# Main_MCU_NuM487KM.net
KiCad netlist of a schematic drawn in Altium Designer
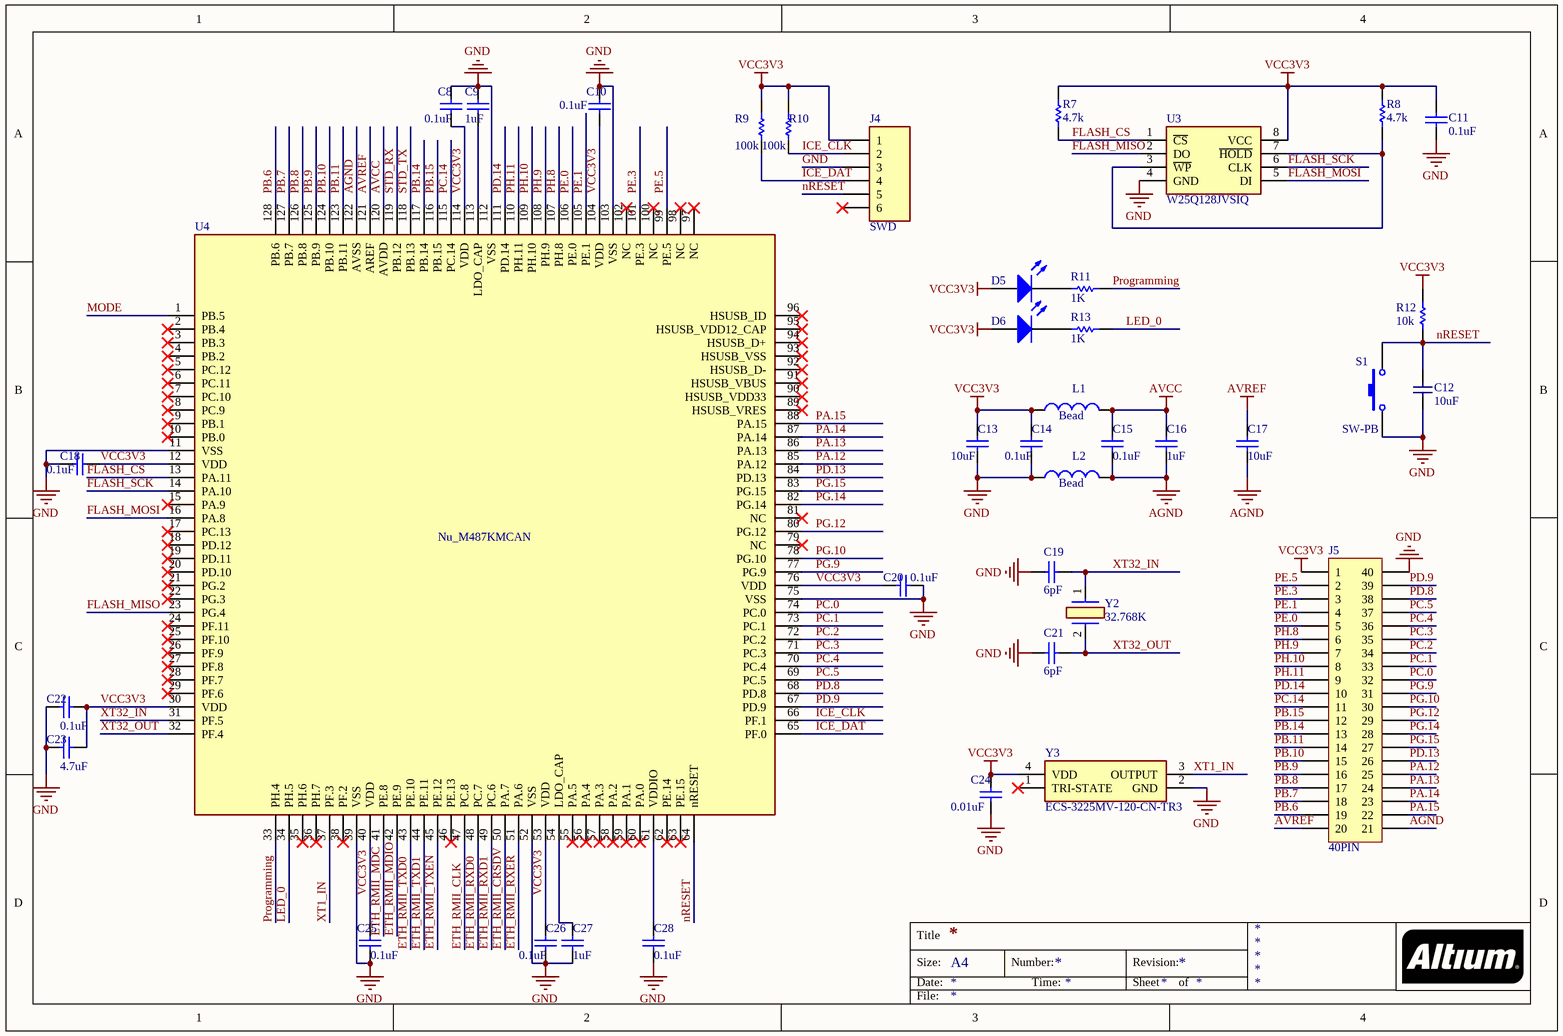
[diagram p0: Main_MCU_NuM487KM.SchDoc]

(export (version "E")
  (design (tool "Eeschema 10.0.6"))
  (components
    (comp (ref "C8")
      (value "0.1uF")
      (footprint "SMD0603")
      (description "Capacitor (Semiconductor SIM Model)")
      (fields (field (name "PUBLISHER") "Altium Limited"))
      (libsource (lib "Miscellaneous Devices") (part "Cap Semi"))
    )
    (comp (ref "C9")
      (value "1uF")
      (footprint "SMD0603")
      (description "Capacitor (Semiconductor SIM Model)")
      (fields (field (name "PUBLISHER") "Altium Limited"))
      (libsource (lib "Miscellaneous Devices") (part "Cap Semi"))
    )
    (comp (ref "C10")
      (value "0.1uF")
      (footprint "SMD0603")
      (description "Capacitor (Semiconductor SIM Model)")
      (fields (field (name "PUBLISHER") "Altium Limited"))
      (libsource (lib "Miscellaneous Devices") (part "Cap Semi"))
    )
    (comp (ref "C11")
      (value "0.1uF")
      (footprint "SMD0603")
      (description "Capacitor (Semiconductor SIM Model)")
      (fields (field (name "PUBLISHER") "Altium Limited"))
      (libsource (lib "Miscellaneous Devices") (part "Cap Semi"))
    )
    (comp (ref "C12")
      (value "10uF")
      (footprint "SMD0603")
      (description "Capacitor (Semiconductor SIM Model)")
      (libsource (lib "SRV8") (part "Cap"))
    )
    (comp (ref "C13")
      (value "10uF")
      (footprint "SMD0603")
      (description "Capacitor (Semiconductor SIM Model)")
      (fields (field (name "PUBLISHER") "Altium Limited"))
      (libsource (lib "Miscellaneous Devices") (part "Cap Semi"))
    )
    (comp (ref "C14")
      (value "0.1uF")
      (footprint "SMD0603")
      (description "Capacitor (Semiconductor SIM Model)")
      (fields (field (name "PUBLISHER") "Altium Limited"))
      (libsource (lib "Miscellaneous Devices") (part "Cap Semi"))
    )
    (comp (ref "C15")
      (value "0.1uF")
      (footprint "SMD0603")
      (description "Capacitor (Semiconductor SIM Model)")
      (fields (field (name "PUBLISHER") "Altium Limited"))
      (libsource (lib "Miscellaneous Devices") (part "Cap Semi"))
    )
    (comp (ref "C16")
      (value "1uF")
      (footprint "SMD0603")
      (description "Capacitor (Semiconductor SIM Model)")
      (fields (field (name "PUBLISHER") "Altium Limited"))
      (libsource (lib "Miscellaneous Devices") (part "Cap Semi"))
    )
    (comp (ref "C17")
      (value "10uF")
      (footprint "SMD0603")
      (description "Capacitor (Semiconductor SIM Model)")
      (fields (field (name "PUBLISHER") "Altium Limited"))
      (libsource (lib "Miscellaneous Devices") (part "Cap Semi"))
    )
    (comp (ref "C18")
      (value "0.1uF")
      (footprint "SMD0603")
      (description "Capacitor (Semiconductor SIM Model)")
      (fields (field (name "PUBLISHER") "Altium Limited"))
      (libsource (lib "Miscellaneous Devices") (part "Cap Semi"))
    )
    (comp (ref "C19")
      (value "6pF")
      (footprint "SMD0603")
      (description "Capacitor (Semiconductor SIM Model)")
      (fields (field (name "PUBLISHER") "Altium Limited"))
      (libsource (lib "Miscellaneous Devices") (part "Cap Semi"))
    )
    (comp (ref "C20")
      (value "0.1uF")
      (footprint "SMD0603")
      (description "Capacitor (Semiconductor SIM Model)")
      (fields (field (name "PUBLISHER") "Altium Limited"))
      (libsource (lib "Miscellaneous Devices") (part "Cap Semi"))
    )
    (comp (ref "C21")
      (value "6pF")
      (footprint "SMD0603")
      (description "Capacitor (Semiconductor SIM Model)")
      (fields (field (name "PUBLISHER") "Altium Limited"))
      (libsource (lib "Miscellaneous Devices") (part "Cap Semi"))
    )
    (comp (ref "C22")
      (value "0.1uF")
      (footprint "SMD0603")
      (description "Capacitor (Semiconductor SIM Model)")
      (fields (field (name "PUBLISHER") "Altium Limited"))
      (libsource (lib "Miscellaneous Devices") (part "Cap Semi"))
    )
    (comp (ref "C23")
      (value "4.7uF")
      (footprint "SMD0603")
      (description "Capacitor (Semiconductor SIM Model)")
      (fields (field (name "PUBLISHER") "Altium Limited"))
      (libsource (lib "Miscellaneous Devices") (part "Cap Semi"))
    )
    (comp (ref "C24")
      (value "0.01uF")
      (footprint "SMD0603")
      (description "Capacitor (Semiconductor SIM Model)")
      (fields (field (name "PUBLISHER") "Altium Limited"))
      (libsource (lib "Miscellaneous Devices") (part "Cap Semi"))
    )
    (comp (ref "C25")
      (value "0.1uF")
      (footprint "SMD0603")
      (description "Capacitor (Semiconductor SIM Model)")
      (fields (field (name "PUBLISHER") "Altium Limited"))
      (libsource (lib "Miscellaneous Devices") (part "Cap Semi"))
    )
    (comp (ref "C26")
      (value "0.1uF")
      (footprint "SMD0603")
      (description "Capacitor (Semiconductor SIM Model)")
      (fields (field (name "PUBLISHER") "Altium Limited"))
      (libsource (lib "Miscellaneous Devices") (part "Cap Semi"))
    )
    (comp (ref "C27")
      (value "1uF")
      (footprint "SMD0603")
      (description "Capacitor (Semiconductor SIM Model)")
      (fields (field (name "PUBLISHER") "Altium Limited"))
      (libsource (lib "Miscellaneous Devices") (part "Cap Semi"))
    )
    (comp (ref "C28")
      (value "0.1uF")
      (footprint "SMD0603")
      (description "Capacitor (Semiconductor SIM Model)")
      (fields (field (name "PUBLISHER") "Altium Limited"))
      (libsource (lib "Miscellaneous Devices") (part "Cap Semi"))
    )
    (comp (ref "D5")
      (value "LED0")
      (footprint "SMD0603_LED")
      (description "Typical INFRARED GaAs LED")
      (fields (field (name "PUBLISHER") "Altium Limited"))
      (libsource (lib "Miscellaneous Devices") (part "LED0"))
    )
    (comp (ref "D6")
      (value "LED0")
      (footprint "SMD0603_LED")
      (description "Typical INFRARED GaAs LED")
      (fields (field (name "PUBLISHER") "Altium Limited"))
      (libsource (lib "Miscellaneous Devices") (part "LED0"))
    )
    (comp (ref "J4") (value "SWD") (footprint "ISP") (libsource (lib "ATSAME54p20a_Ethernet") (part "SWD")))
    (comp (ref "J5")
      (value "40PIN")
      (footprint "40PIN")
      (libsource (lib "ATSAME54p20a_Ethernet") (part "2x20_header"))
    )
    (comp (ref "L1")
      (value "Bead")
      (footprint "SMD0603")
      (description "Inductor")
      (fields (field (name "PUBLISHER") "Altium Limited"))
      (libsource (lib "Miscellaneous Devices") (part "Inductor"))
    )
    (comp (ref "L2")
      (value "Bead")
      (footprint "SMD0603")
      (description "Inductor")
      (fields (field (name "PUBLISHER") "Altium Limited"))
      (libsource (lib "Miscellaneous Devices") (part "Inductor"))
    )
    (comp (ref "R7")
      (value "4.7k")
      (footprint "SMD0603")
      (description "Semiconductor Resistor")
      (libsource (lib "*") (part "Res"))
    )
    (comp (ref "R8")
      (value "4.7k")
      (footprint "SMD0603")
      (description "Semiconductor Resistor")
      (libsource (lib "*") (part "Res"))
    )
    (comp (ref "R9")
      (value "100k")
      (footprint "SMD0603")
      (description "Semiconductor Resistor")
      (fields (field (name "Comment") "100K"))
      (libsource (lib "*") (part "Res"))
    )
    (comp (ref "R10")
      (value "100k")
      (footprint "SMD0603")
      (description "Semiconductor Resistor")
      (fields (field (name "Comment") "100K"))
      (libsource (lib "*") (part "Res"))
    )
    (comp (ref "R11")
      (value "1K")
      (footprint "SMD0603")
      (description "Semiconductor Resistor")
      (fields (field (name "PUBLISHER") "Altium Limited"))
      (libsource (lib "Miscellaneous Devices") (part "Res Semi"))
    )
    (comp (ref "R12")
      (value "10k")
      (footprint "SMD0603")
      (description "Semiconductor Resistor")
      (fields (field (name "Comment") "10K"))
      (libsource (lib "*") (part "Res"))
    )
    (comp (ref "R13")
      (value "1K")
      (footprint "SMD0603")
      (description "Semiconductor Resistor")
      (fields (field (name "PUBLISHER") "Altium Limited"))
      (libsource (lib "Miscellaneous Devices") (part "Res Semi"))
    )
    (comp (ref "S1")
      (value "SW-PB")
      (footprint "Button")
      (description "Switch")
      (fields (field (name "PUBLISHER") "Altium Limited"))
      (libsource (lib "Miscellaneous Devices") (part "SW-PB"))
    )
    (comp (ref "U3")
      (value "W25Q128JVSIQ")
      (footprint "ATSAME54p20a_Ethernet:SOIC127P790X216-8N")
      (description "Integrated Circuit")
      (fields (field (name "MOUSER2 PART NUMBER") "454-W25Q128JVSIQ"))
      (libsource (lib "ATSAME54p20a_Ethernet") (part "W25Q128JVSIQ"))
    )
    (comp (ref "U4")
      (value "Nu_M487KMCAN")
      (footprint "QFP40P1600X1600X120-128N")
      (description "Integrated Circuit")
      (libsource (lib "NuM487_DEVB") (part "Nu_M487KMCAN"))
    )
    (comp (ref "Y2")
      (value "32.768K")
      (footprint "ATSAME54p20a_Ethernet:ECS327634RTR")
      (description "Crystal or Oscillator")
      (fields (field (name "MANUFACTURER_PART_NUMBER") "ECS-.327-6-34R-TR"))
      (libsource (lib "ATSAME54_DEVB") (part "ECS-.327-6-34R-TR"))
    )
    (comp (ref "Y3")
      (value "ECS-3225MV-120-CN-TR3")
      (footprint "OSC3225")
      (description "Crystal or Oscillator")
      (libsource (lib "ATSAME54p20a_Ethernet") (part "ECS-3225MV-120-CN-TR3"))
    )
  )
  (nets
    (net (code "1") (name "/ETH_RMII_CLK") (class "Default")
      (node (ref "U4") (pin "47") (pinfunction "PC.8_47") (pintype "passive"))
    )
    (net (code "2") (name "/ETH_RMII_CRSDV") (class "Default")
      (node (ref "U4") (pin "50") (pinfunction "PA.7_50") (pintype "passive"))
    )
    (net (code "3") (name "/ETH_RMII_MDC") (class "Default")
      (node (ref "U4") (pin "41") (pinfunction "PE.8_41") (pintype "passive"))
    )
    (net (code "4") (name "/ETH_RMII_MDIO") (class "Default")
      (node (ref "U4") (pin "42") (pinfunction "PE.9_42") (pintype "passive"))
    )
    (net (code "5") (name "/ETH_RMII_RXD0") (class "Default")
      (node (ref "U4") (pin "48") (pinfunction "PC.7_48") (pintype "passive"))
    )
    (net (code "6") (name "/ETH_RMII_RXD1") (class "Default")
      (node (ref "U4") (pin "49") (pinfunction "PC.6_49") (pintype "passive"))
    )
    (net (code "7") (name "/ETH_RMII_RXER") (class "Default")
      (node (ref "U4") (pin "51") (pinfunction "PA.6_51") (pintype "passive"))
    )
    (net (code "8") (name "/ETH_RMII_TXD0") (class "Default")
      (node (ref "U4") (pin "43") (pinfunction "PE.10_43") (pintype "passive"))
    )
    (net (code "9") (name "/ETH_RMII_TXD1") (class "Default")
      (node (ref "U4") (pin "44") (pinfunction "PE.11_44") (pintype "passive"))
    )
    (net (code "10") (name "/ETH_RMII_TXEN") (class "Default")
      (node (ref "U4") (pin "45") (pinfunction "PE.12_45") (pintype "passive"))
    )
    (net (code "11") (name "/FLASH_CS") (class "Default")
      (node (ref "R7") (pin "1") (pinfunction "1_1") (pintype "passive"))
      (node (ref "U3") (pin "1") (pinfunction "~{CS}_1") (pintype "passive"))
      (node (ref "U4") (pin "13") (pinfunction "PA.11_13") (pintype "passive"))
    )
    (net (code "12") (name "/FLASH_MISO") (class "Default")
      (node (ref "U3") (pin "2") (pinfunction "DO_2") (pintype "passive"))
      (node (ref "U4") (pin "23") (pinfunction "PG.4_23") (pintype "passive"))
    )
    (net (code "13") (name "/FLASH_MOSI") (class "Default")
      (node (ref "U3") (pin "5") (pinfunction "DI_5") (pintype "passive"))
      (node (ref "U4") (pin "16") (pinfunction "PA.8_16") (pintype "passive"))
    )
    (net (code "14") (name "/FLASH_SCK") (class "Default")
      (node (ref "U3") (pin "6") (pinfunction "CLK_6") (pintype "passive"))
      (node (ref "U4") (pin "14") (pinfunction "PA.10_14") (pintype "passive"))
    )
    (net (code "15") (name "/ICE_CLK") (class "Default")
      (node (ref "J4") (pin "2") (pinfunction "2_2") (pintype "passive"))
      (node (ref "R10") (pin "1") (pinfunction "1_1") (pintype "passive"))
      (node (ref "U4") (pin "66") (pinfunction "PF.1_66") (pintype "passive"))
    )
    (net (code "16") (name "/ICE_DAT") (class "Default")
      (node (ref "J4") (pin "4") (pinfunction "4_4") (pintype "passive"))
      (node (ref "R9") (pin "1") (pinfunction "1_1") (pintype "passive"))
      (node (ref "U4") (pin "65") (pinfunction "PF.0_65") (pintype "passive"))
    )
    (net (code "17") (name "/LED_0") (class "Default")
      (node (ref "R13") (pin "1") (pinfunction "1_1") (pintype "passive"))
      (node (ref "U4") (pin "34") (pinfunction "PH.5_34") (pintype "passive"))
    )
    (net (code "18") (name "/MODE") (class "Default")
      (node (ref "U4") (pin "1") (pinfunction "PB.5_1") (pintype "passive"))
    )
    (net (code "19") (name "/PA.12") (class "Default")
      (node (ref "J5") (pin "25") (pinfunction "25_25") (pintype "passive"))
      (node (ref "U4") (pin "85") (pinfunction "PA.12_85") (pintype "passive"))
    )
    (net (code "20") (name "/PA.13") (class "Default")
      (node (ref "J5") (pin "24") (pinfunction "24_24") (pintype "passive"))
      (node (ref "U4") (pin "86") (pinfunction "PA.13_86") (pintype "passive"))
    )
    (net (code "21") (name "/PA.14") (class "Default")
      (node (ref "J5") (pin "23") (pinfunction "23_23") (pintype "passive"))
      (node (ref "U4") (pin "87") (pinfunction "PA.14_87") (pintype "passive"))
    )
    (net (code "22") (name "/PA.15") (class "Default")
      (node (ref "J5") (pin "22") (pinfunction "22_22") (pintype "passive"))
      (node (ref "U4") (pin "88") (pinfunction "PA.15_88") (pintype "passive"))
    )
    (net (code "23") (name "/PB.6") (class "Default")
      (node (ref "J5") (pin "19") (pinfunction "19_19") (pintype "passive"))
      (node (ref "U4") (pin "128") (pinfunction "PB.6_128") (pintype "passive"))
    )
    (net (code "24") (name "/PB.7") (class "Default")
      (node (ref "J5") (pin "18") (pinfunction "18_18") (pintype "passive"))
      (node (ref "U4") (pin "127") (pinfunction "PB.7_127") (pintype "passive"))
    )
    (net (code "25") (name "/PB.8") (class "Default")
      (node (ref "J5") (pin "17") (pinfunction "17_17") (pintype "passive"))
      (node (ref "U4") (pin "126") (pinfunction "PB.8_126") (pintype "passive"))
    )
    (net (code "26") (name "/PB.9") (class "Default")
      (node (ref "J5") (pin "16") (pinfunction "16_16") (pintype "passive"))
      (node (ref "U4") (pin "125") (pinfunction "PB.9_125") (pintype "passive"))
    )
    (net (code "27") (name "/PB.10") (class "Default")
      (node (ref "J5") (pin "15") (pinfunction "15_15") (pintype "passive"))
      (node (ref "U4") (pin "124") (pinfunction "PB.10_124") (pintype "passive"))
    )
    (net (code "28") (name "/PB.11") (class "Default")
      (node (ref "J5") (pin "14") (pinfunction "14_14") (pintype "passive"))
      (node (ref "U4") (pin "123") (pinfunction "PB.11_123") (pintype "passive"))
    )
    (net (code "29") (name "/PB.14") (class "Default")
      (node (ref "J5") (pin "13") (pinfunction "13_13") (pintype "passive"))
      (node (ref "U4") (pin "117") (pinfunction "PB.14_117") (pintype "passive"))
    )
    (net (code "30") (name "/PB.15") (class "Default")
      (node (ref "J5") (pin "12") (pinfunction "12_12") (pintype "passive"))
      (node (ref "U4") (pin "116") (pinfunction "PB.15_116") (pintype "passive"))
    )
    (net (code "31") (name "/PC.0") (class "Default")
      (node (ref "J5") (pin "32") (pinfunction "32_32") (pintype "passive"))
      (node (ref "U4") (pin "74") (pinfunction "PC.0_74") (pintype "passive"))
    )
    (net (code "32") (name "/PC.1") (class "Default")
      (node (ref "J5") (pin "33") (pinfunction "33_33") (pintype "passive"))
      (node (ref "U4") (pin "73") (pinfunction "PC.1_73") (pintype "passive"))
    )
    (net (code "33") (name "/PC.2") (class "Default")
      (node (ref "J5") (pin "34") (pinfunction "34_34") (pintype "passive"))
      (node (ref "U4") (pin "72") (pinfunction "PC.2_72") (pintype "passive"))
    )
    (net (code "34") (name "/PC.3") (class "Default")
      (node (ref "J5") (pin "35") (pinfunction "35_35") (pintype "passive"))
      (node (ref "U4") (pin "71") (pinfunction "PC.3_71") (pintype "passive"))
    )
    (net (code "35") (name "/PC.4") (class "Default")
      (node (ref "J5") (pin "36") (pinfunction "36_36") (pintype "passive"))
      (node (ref "U4") (pin "70") (pinfunction "PC.4_70") (pintype "passive"))
    )
    (net (code "36") (name "/PC.5") (class "Default")
      (node (ref "J5") (pin "37") (pinfunction "37_37") (pintype "passive"))
      (node (ref "U4") (pin "69") (pinfunction "PC.5_69") (pintype "passive"))
    )
    (net (code "37") (name "/PC.14") (class "Default")
      (node (ref "J5") (pin "11") (pinfunction "11_11") (pintype "passive"))
      (node (ref "U4") (pin "115") (pinfunction "PC.14_115") (pintype "passive"))
    )
    (net (code "38") (name "/PD.8") (class "Default")
      (node (ref "J5") (pin "38") (pinfunction "38_38") (pintype "passive"))
      (node (ref "U4") (pin "68") (pinfunction "PD.8_68") (pintype "passive"))
    )
    (net (code "39") (name "/PD.9") (class "Default")
      (node (ref "J5") (pin "39") (pinfunction "39_39") (pintype "passive"))
      (node (ref "U4") (pin "67") (pinfunction "PD.9_67") (pintype "passive"))
    )
    (net (code "40") (name "/PD.13") (class "Default")
      (node (ref "J5") (pin "26") (pinfunction "26_26") (pintype "passive"))
      (node (ref "U4") (pin "84") (pinfunction "PD.13_84") (pintype "passive"))
    )
    (net (code "41") (name "/PD.14") (class "Default")
      (node (ref "J5") (pin "10") (pinfunction "10_10") (pintype "passive"))
      (node (ref "U4") (pin "111") (pinfunction "PD.14_111") (pintype "passive"))
    )
    (net (code "42") (name "/PE.0") (class "Default")
      (node (ref "J5") (pin "5") (pinfunction "5_5") (pintype "passive"))
      (node (ref "U4") (pin "106") (pinfunction "PE.0_106") (pintype "passive"))
    )
    (net (code "43") (name "/PE.1") (class "Default")
      (node (ref "J5") (pin "4") (pinfunction "4_4") (pintype "passive"))
      (node (ref "U4") (pin "105") (pinfunction "PE.1_105") (pintype "passive"))
    )
    (net (code "44") (name "/PE.3") (class "Default")
      (node (ref "J5") (pin "3") (pinfunction "3_3") (pintype "passive"))
      (node (ref "U4") (pin "101") (pinfunction "PE.3_101") (pintype "passive"))
    )
    (net (code "45") (name "/PE.5") (class "Default")
      (node (ref "J5") (pin "2") (pinfunction "2_2") (pintype "passive"))
      (node (ref "U4") (pin "99") (pinfunction "PE.5_99") (pintype "passive"))
    )
    (net (code "46") (name "/PG.9") (class "Default")
      (node (ref "J5") (pin "31") (pinfunction "31_31") (pintype "passive"))
      (node (ref "U4") (pin "77") (pinfunction "PG.9_77") (pintype "passive"))
    )
    (net (code "47") (name "/PG.10") (class "Default")
      (node (ref "J5") (pin "30") (pinfunction "30_30") (pintype "passive"))
      (node (ref "U4") (pin "78") (pinfunction "PG.10_78") (pintype "passive"))
    )
    (net (code "48") (name "/PG.12") (class "Default")
      (node (ref "J5") (pin "29") (pinfunction "29_29") (pintype "passive"))
      (node (ref "U4") (pin "80") (pinfunction "PG.12_80") (pintype "passive"))
    )
    (net (code "49") (name "/PG.14") (class "Default")
      (node (ref "J5") (pin "28") (pinfunction "28_28") (pintype "passive"))
      (node (ref "U4") (pin "82") (pinfunction "PG.14_82") (pintype "passive"))
    )
    (net (code "50") (name "/PG.15") (class "Default")
      (node (ref "J5") (pin "27") (pinfunction "27_27") (pintype "passive"))
      (node (ref "U4") (pin "83") (pinfunction "PG.15_83") (pintype "passive"))
    )
    (net (code "51") (name "/PH.8") (class "Default")
      (node (ref "J5") (pin "6") (pinfunction "6_6") (pintype "passive"))
      (node (ref "U4") (pin "107") (pinfunction "PH.8_107") (pintype "passive"))
    )
    (net (code "52") (name "/PH.9") (class "Default")
      (node (ref "J5") (pin "7") (pinfunction "7_7") (pintype "passive"))
      (node (ref "U4") (pin "108") (pinfunction "PH.9_108") (pintype "passive"))
    )
    (net (code "53") (name "/PH.10") (class "Default")
      (node (ref "J5") (pin "8") (pinfunction "8_8") (pintype "passive"))
      (node (ref "U4") (pin "109") (pinfunction "PH.10_109") (pintype "passive"))
    )
    (net (code "54") (name "/PH.11") (class "Default")
      (node (ref "J5") (pin "9") (pinfunction "9_9") (pintype "passive"))
      (node (ref "U4") (pin "110") (pinfunction "PH.11_110") (pintype "passive"))
    )
    (net (code "55") (name "/Programming") (class "Default")
      (node (ref "R11") (pin "1") (pinfunction "1_1") (pintype "passive"))
      (node (ref "U4") (pin "33") (pinfunction "PH.4_33") (pintype "passive"))
    )
    (net (code "56") (name "/STD_RX") (class "Default")
      (node (ref "U4") (pin "119") (pinfunction "PB.12_119") (pintype "passive"))
    )
    (net (code "57") (name "/STD_TX") (class "Default")
      (node (ref "U4") (pin "118") (pinfunction "PB.13_118") (pintype "passive"))
    )
    (net (code "58") (name "/XT1_IN") (class "Default")
      (node (ref "U4") (pin "37") (pinfunction "PF.3_37") (pintype "passive"))
      (node (ref "Y3") (pin "3") (pinfunction "OUTPUT_3") (pintype "passive"))
    )
    (net (code "59") (name "/XT32_IN") (class "Default")
      (node (ref "C19") (pin "1") (pinfunction "1_1") (pintype "passive"))
      (node (ref "U4") (pin "31") (pinfunction "PF.5_31") (pintype "passive"))
      (node (ref "Y2") (pin "1") (pinfunction "OUT/IN_1") (pintype "passive"))
    )
    (net (code "60") (name "/XT32_OUT") (class "Default")
      (node (ref "C21") (pin "1") (pinfunction "1_1") (pintype "passive"))
      (node (ref "U4") (pin "32") (pinfunction "PF.4_32") (pintype "passive"))
      (node (ref "Y2") (pin "2") (pinfunction "OUT/IN_2") (pintype "passive"))
    )
    (net (code "61") (name "/nRESET") (class "Default")
      (node (ref "C12") (pin "2") (pinfunction "2_2") (pintype "passive"))
      (node (ref "J4") (pin "5") (pinfunction "5_5") (pintype "passive"))
      (node (ref "R12") (pin "1") (pinfunction "1_1") (pintype "passive"))
      (node (ref "S1") (pin "2") (pinfunction "2_2") (pintype "passive"))
      (node (ref "U4") (pin "64") (pinfunction "nRESET_64") (pintype "passive"))
    )
    (net (code "62") (name "AGND") (class "Default")
      (node (ref "C15") (pin "2") (pinfunction "2_2") (pintype "passive"))
      (node (ref "C16") (pin "2") (pinfunction "2_2") (pintype "passive"))
      (node (ref "C17") (pin "2") (pinfunction "2_2") (pintype "passive"))
      (node (ref "J5") (pin "21") (pinfunction "21_21") (pintype "passive"))
      (node (ref "L2") (pin "2") (pinfunction "2_2") (pintype "passive"))
      (node (ref "U4") (pin "122") (pinfunction "AVSS_122") (pintype "passive"))
    )
    (net (code "63") (name "AVCC") (class "Default")
      (node (ref "C15") (pin "1") (pinfunction "1_1") (pintype "passive"))
      (node (ref "C16") (pin "1") (pinfunction "1_1") (pintype "passive"))
      (node (ref "L1") (pin "2") (pinfunction "2_2") (pintype "passive"))
      (node (ref "U4") (pin "120") (pinfunction "AVDD_120") (pintype "passive"))
    )
    (net (code "64") (name "AVREF") (class "Default")
      (node (ref "C17") (pin "1") (pinfunction "1_1") (pintype "passive"))
      (node (ref "J5") (pin "20") (pinfunction "20_20") (pintype "passive"))
      (node (ref "U4") (pin "121") (pinfunction "AREF_121") (pintype "passive"))
    )
    (net (code "65") (name "GND") (class "Default")
      (node (ref "C10") (pin "2") (pinfunction "2_2") (pintype "passive"))
      (node (ref "C11") (pin "2") (pinfunction "2_2") (pintype "passive"))
      (node (ref "C12") (pin "1") (pinfunction "1_1") (pintype "passive"))
      (node (ref "C13") (pin "2") (pinfunction "2_2") (pintype "passive"))
      (node (ref "C14") (pin "2") (pinfunction "2_2") (pintype "passive"))
      (node (ref "C18") (pin "2") (pinfunction "2_2") (pintype "passive"))
      (node (ref "C19") (pin "2") (pinfunction "2_2") (pintype "passive"))
      (node (ref "C20") (pin "1") (pinfunction "1_1") (pintype "passive"))
      (node (ref "C21") (pin "2") (pinfunction "2_2") (pintype "passive"))
      (node (ref "C22") (pin "2") (pinfunction "2_2") (pintype "passive"))
      (node (ref "C23") (pin "2") (pinfunction "2_2") (pintype "passive"))
      (node (ref "C24") (pin "1") (pinfunction "1_1") (pintype "passive"))
      (node (ref "C25") (pin "1") (pinfunction "1_1") (pintype "passive"))
      (node (ref "C26") (pin "1") (pinfunction "1_1") (pintype "passive"))
      (node (ref "C27") (pin "1") (pinfunction "1_1") (pintype "passive"))
      (node (ref "C28") (pin "1") (pinfunction "1_1") (pintype "passive"))
      (node (ref "C8") (pin "2") (pinfunction "2_2") (pintype "passive"))
      (node (ref "C9") (pin "1") (pinfunction "1_1") (pintype "passive"))
      (node (ref "J4") (pin "3") (pinfunction "3_3") (pintype "passive"))
      (node (ref "J5") (pin "40") (pinfunction "40_40") (pintype "passive"))
      (node (ref "L2") (pin "1") (pinfunction "1_1") (pintype "passive"))
      (node (ref "S1") (pin "1") (pinfunction "1_1") (pintype "passive"))
      (node (ref "U3") (pin "4") (pinfunction "GND_4") (pintype "passive"))
      (node (ref "U4") (pin "103") (pinfunction "VSS_103") (pintype "passive"))
      (node (ref "U4") (pin "11") (pinfunction "VSS_11") (pintype "passive"))
      (node (ref "U4") (pin "112") (pinfunction "VSS_112") (pintype "passive"))
      (node (ref "U4") (pin "39") (pinfunction "VSS_39") (pintype "passive"))
      (node (ref "U4") (pin "52") (pinfunction "VSS_52") (pintype "passive"))
      (node (ref "U4") (pin "75") (pinfunction "VSS_75") (pintype "passive"))
      (node (ref "Y3") (pin "2") (pinfunction "GND_2") (pintype "passive"))
    )
    (net (code "66") (name "Net-(C9-Pad2)") (class "Default")
      (node (ref "C9") (pin "2") (pinfunction "2_2") (pintype "passive"))
      (node (ref "U4") (pin "113") (pinfunction "LDO_CAP_113") (pintype "passive"))
    )
    (net (code "67") (name "Net-(C27-Pad2)") (class "Default")
      (node (ref "C27") (pin "2") (pinfunction "2_2") (pintype "passive"))
      (node (ref "U4") (pin "54") (pinfunction "LDO_CAP_54") (pintype "passive"))
    )
    (net (code "68") (name "Net-(D5-K)") (class "Default")
      (node (ref "D5") (pin "2") (pinfunction "K_2") (pintype "passive"))
      (node (ref "R11") (pin "2") (pinfunction "2_2") (pintype "passive"))
    )
    (net (code "69") (name "Net-(D6-K)") (class "Default")
      (node (ref "D6") (pin "2") (pinfunction "K_2") (pintype "passive"))
      (node (ref "R13") (pin "2") (pinfunction "2_2") (pintype "passive"))
    )
    (net (code "70") (name "Net-(U3-~{HOLD})") (class "Default")
      (node (ref "R8") (pin "1") (pinfunction "1_1") (pintype "passive"))
      (node (ref "U3") (pin "3") (pinfunction "~{WP}_3") (pintype "passive"))
      (node (ref "U3") (pin "7") (pinfunction "~{HOLD}_7") (pintype "passive"))
    )
    (net (code "71") (name "Net-(U4-VDDIO)") (class "Default")
      (node (ref "C28") (pin "2") (pinfunction "2_2") (pintype "passive"))
      (node (ref "U4") (pin "61") (pinfunction "VDDIO_61") (pintype "passive"))
    )
    (net (code "72") (name "VCC3V3") (class "Default")
      (node (ref "C10") (pin "1") (pinfunction "1_1") (pintype "passive"))
      (node (ref "C11") (pin "1") (pinfunction "1_1") (pintype "passive"))
      (node (ref "C13") (pin "1") (pinfunction "1_1") (pintype "passive"))
      (node (ref "C14") (pin "1") (pinfunction "1_1") (pintype "passive"))
      (node (ref "C18") (pin "1") (pinfunction "1_1") (pintype "passive"))
      (node (ref "C20") (pin "2") (pinfunction "2_2") (pintype "passive"))
      (node (ref "C22") (pin "1") (pinfunction "1_1") (pintype "passive"))
      (node (ref "C23") (pin "1") (pinfunction "1_1") (pintype "passive"))
      (node (ref "C24") (pin "2") (pinfunction "2_2") (pintype "passive"))
      (node (ref "C25") (pin "2") (pinfunction "2_2") (pintype "passive"))
      (node (ref "C26") (pin "2") (pinfunction "2_2") (pintype "passive"))
      (node (ref "C8") (pin "1") (pinfunction "1_1") (pintype "passive"))
      (node (ref "D5") (pin "1") (pinfunction "A_1") (pintype "passive"))
      (node (ref "D6") (pin "1") (pinfunction "A_1") (pintype "passive"))
      (node (ref "J4") (pin "1") (pinfunction "1_1") (pintype "passive"))
      (node (ref "J5") (pin "1") (pinfunction "1_1") (pintype "passive"))
      (node (ref "L1") (pin "1") (pinfunction "1_1") (pintype "passive"))
      (node (ref "R10") (pin "2") (pinfunction "2_2") (pintype "passive"))
      (node (ref "R12") (pin "2") (pinfunction "2_2") (pintype "passive"))
      (node (ref "R7") (pin "2") (pinfunction "2_2") (pintype "passive"))
      (node (ref "R8") (pin "2") (pinfunction "2_2") (pintype "passive"))
      (node (ref "R9") (pin "2") (pinfunction "2_2") (pintype "passive"))
      (node (ref "U3") (pin "8") (pinfunction "VCC_8") (pintype "passive"))
      (node (ref "U4") (pin "104") (pinfunction "VDD_104") (pintype "passive"))
      (node (ref "U4") (pin "114") (pinfunction "VDD_114") (pintype "passive"))
      (node (ref "U4") (pin "12") (pinfunction "VDD_12") (pintype "passive"))
      (node (ref "U4") (pin "30") (pinfunction "VDD_30") (pintype "passive"))
      (node (ref "U4") (pin "40") (pinfunction "VDD_40") (pintype "passive"))
      (node (ref "U4") (pin "53") (pinfunction "VDD_53") (pintype "passive"))
      (node (ref "U4") (pin "76") (pinfunction "VDD_76") (pintype "passive"))
      (node (ref "Y3") (pin "4") (pinfunction "VDD_4") (pintype "passive"))
    )
    (net (code "73") (name "unconnected-(J4-Pad6)") (class "Default")
      (node (ref "J4") (pin "6") (pinfunction "6_6") (pintype "passive+no_connect"))
    )
    (net (code "74") (name "unconnected-(U4-HSUSB_D+-Pad94)") (class "Default")
      (node (ref "U4") (pin "94") (pinfunction "HSUSB_D+_94") (pintype "passive+no_connect"))
    )
    (net (code "75") (name "unconnected-(U4-HSUSB_D--Pad92)") (class "Default")
      (node (ref "U4") (pin "92") (pinfunction "HSUSB_D-_92") (pintype "passive+no_connect"))
    )
    (net (code "76") (name "unconnected-(U4-HSUSB_ID-Pad96)") (class "Default")
      (node (ref "U4") (pin "96") (pinfunction "HSUSB_ID_96") (pintype "passive+no_connect"))
    )
    (net (code "77") (name "unconnected-(U4-HSUSB_VBUS-Pad91)") (class "Default")
      (node (ref "U4") (pin "91") (pinfunction "HSUSB_VBUS_91") (pintype "passive+no_connect"))
    )
    (net (code "78") (name "unconnected-(U4-HSUSB_VDD12_CAP-Pad95)") (class "Default")
      (node (ref "U4") (pin "95") (pinfunction "HSUSB_VDD12_CAP_95") (pintype "passive+no_connect"))
    )
    (net (code "79") (name "unconnected-(U4-HSUSB_VDD33-Pad90)") (class "Default")
      (node (ref "U4") (pin "90") (pinfunction "HSUSB_VDD33_90") (pintype "passive+no_connect"))
    )
    (net (code "80") (name "unconnected-(U4-HSUSB_VRES-Pad89)") (class "Default")
      (node (ref "U4") (pin "89") (pinfunction "HSUSB_VRES_89") (pintype "passive+no_connect"))
    )
    (net (code "81") (name "unconnected-(U4-HSUSB_VSS-Pad93)") (class "Default")
      (node (ref "U4") (pin "93") (pinfunction "HSUSB_VSS_93") (pintype "passive+no_connect"))
    )
    (net (code "82") (name "unconnected-(U4-NC-Pad79)") (class "Default")
      (node (ref "U4") (pin "79") (pinfunction "NC_79") (pintype "passive+no_connect"))
    )
    (net (code "83") (name "unconnected-(U4-NC-Pad81)") (class "Default")
      (node (ref "U4") (pin "81") (pinfunction "NC_81") (pintype "passive+no_connect"))
    )
    (net (code "84") (name "unconnected-(U4-NC-Pad97)") (class "Default")
      (node (ref "U4") (pin "97") (pinfunction "NC_97") (pintype "passive+no_connect"))
    )
    (net (code "85") (name "unconnected-(U4-NC-Pad98)") (class "Default")
      (node (ref "U4") (pin "98") (pinfunction "NC_98") (pintype "passive+no_connect"))
    )
    (net (code "86") (name "unconnected-(U4-NC-Pad100)") (class "Default")
      (node (ref "U4") (pin "100") (pinfunction "NC_100") (pintype "passive+no_connect"))
    )
    (net (code "87") (name "unconnected-(U4-NC-Pad102)") (class "Default")
      (node (ref "U4") (pin "102") (pinfunction "NC_102") (pintype "passive+no_connect"))
    )
    (net (code "88") (name "unconnected-(U4-PA.0-Pad60)") (class "Default")
      (node (ref "U4") (pin "60") (pinfunction "PA.0_60") (pintype "passive+no_connect"))
    )
    (net (code "89") (name "unconnected-(U4-PA.1-Pad59)") (class "Default")
      (node (ref "U4") (pin "59") (pinfunction "PA.1_59") (pintype "passive+no_connect"))
    )
    (net (code "90") (name "unconnected-(U4-PA.2-Pad58)") (class "Default")
      (node (ref "U4") (pin "58") (pinfunction "PA.2_58") (pintype "passive+no_connect"))
    )
    (net (code "91") (name "unconnected-(U4-PA.3-Pad57)") (class "Default")
      (node (ref "U4") (pin "57") (pinfunction "PA.3_57") (pintype "passive+no_connect"))
    )
    (net (code "92") (name "unconnected-(U4-PA.4-Pad56)") (class "Default")
      (node (ref "U4") (pin "56") (pinfunction "PA.4_56") (pintype "passive+no_connect"))
    )
    (net (code "93") (name "unconnected-(U4-PA.5-Pad55)") (class "Default")
      (node (ref "U4") (pin "55") (pinfunction "PA.5_55") (pintype "passive+no_connect"))
    )
    (net (code "94") (name "unconnected-(U4-PA.9-Pad15)") (class "Default")
      (node (ref "U4") (pin "15") (pinfunction "PA.9_15") (pintype "passive+no_connect"))
    )
    (net (code "95") (name "unconnected-(U4-PB.0-Pad10)") (class "Default")
      (node (ref "U4") (pin "10") (pinfunction "PB.0_10") (pintype "passive+no_connect"))
    )
    (net (code "96") (name "unconnected-(U4-PB.1-Pad9)") (class "Default")
      (node (ref "U4") (pin "9") (pinfunction "PB.1_9") (pintype "passive+no_connect"))
    )
    (net (code "97") (name "unconnected-(U4-PB.2-Pad4)") (class "Default")
      (node (ref "U4") (pin "4") (pinfunction "PB.2_4") (pintype "passive+no_connect"))
    )
    (net (code "98") (name "unconnected-(U4-PB.3-Pad3)") (class "Default")
      (node (ref "U4") (pin "3") (pinfunction "PB.3_3") (pintype "passive+no_connect"))
    )
    (net (code "99") (name "unconnected-(U4-PB.4-Pad2)") (class "Default")
      (node (ref "U4") (pin "2") (pinfunction "PB.4_2") (pintype "passive+no_connect"))
    )
    (net (code "100") (name "unconnected-(U4-PC.9-Pad8)") (class "Default")
      (node (ref "U4") (pin "8") (pinfunction "PC.9_8") (pintype "passive+no_connect"))
    )
    (net (code "101") (name "unconnected-(U4-PC.10-Pad7)") (class "Default")
      (node (ref "U4") (pin "7") (pinfunction "PC.10_7") (pintype "passive+no_connect"))
    )
    (net (code "102") (name "unconnected-(U4-PC.11-Pad6)") (class "Default")
      (node (ref "U4") (pin "6") (pinfunction "PC.11_6") (pintype "passive+no_connect"))
    )
    (net (code "103") (name "unconnected-(U4-PC.12-Pad5)") (class "Default")
      (node (ref "U4") (pin "5") (pinfunction "PC.12_5") (pintype "passive+no_connect"))
    )
    (net (code "104") (name "unconnected-(U4-PC.13-Pad17)") (class "Default")
      (node (ref "U4") (pin "17") (pinfunction "PC.13_17") (pintype "passive+no_connect"))
    )
    (net (code "105") (name "unconnected-(U4-PD.10-Pad20)") (class "Default")
      (node (ref "U4") (pin "20") (pinfunction "PD.10_20") (pintype "passive+no_connect"))
    )
    (net (code "106") (name "unconnected-(U4-PD.11-Pad19)") (class "Default")
      (node (ref "U4") (pin "19") (pinfunction "PD.11_19") (pintype "passive+no_connect"))
    )
    (net (code "107") (name "unconnected-(U4-PD.12-Pad18)") (class "Default")
      (node (ref "U4") (pin "18") (pinfunction "PD.12_18") (pintype "passive+no_connect"))
    )
    (net (code "108") (name "unconnected-(U4-PE.13-Pad46)") (class "Default")
      (node (ref "U4") (pin "46") (pinfunction "PE.13_46") (pintype "passive+no_connect"))
    )
    (net (code "109") (name "unconnected-(U4-PE.14-Pad62)") (class "Default")
      (node (ref "U4") (pin "62") (pinfunction "PE.14_62") (pintype "passive+no_connect"))
    )
    (net (code "110") (name "unconnected-(U4-PE.15-Pad63)") (class "Default")
      (node (ref "U4") (pin "63") (pinfunction "PE.15_63") (pintype "passive+no_connect"))
    )
    (net (code "111") (name "unconnected-(U4-PF.2-Pad38)") (class "Default")
      (node (ref "U4") (pin "38") (pinfunction "PF.2_38") (pintype "passive+no_connect"))
    )
    (net (code "112") (name "unconnected-(U4-PF.6-Pad29)") (class "Default")
      (node (ref "U4") (pin "29") (pinfunction "PF.6_29") (pintype "passive+no_connect"))
    )
    (net (code "113") (name "unconnected-(U4-PF.7-Pad28)") (class "Default")
      (node (ref "U4") (pin "28") (pinfunction "PF.7_28") (pintype "passive+no_connect"))
    )
    (net (code "114") (name "unconnected-(U4-PF.8-Pad27)") (class "Default")
      (node (ref "U4") (pin "27") (pinfunction "PF.8_27") (pintype "passive+no_connect"))
    )
    (net (code "115") (name "unconnected-(U4-PF.9-Pad26)") (class "Default")
      (node (ref "U4") (pin "26") (pinfunction "PF.9_26") (pintype "passive+no_connect"))
    )
    (net (code "116") (name "unconnected-(U4-PF.10-Pad25)") (class "Default")
      (node (ref "U4") (pin "25") (pinfunction "PF.10_25") (pintype "passive+no_connect"))
    )
    (net (code "117") (name "unconnected-(U4-PF.11-Pad24)") (class "Default")
      (node (ref "U4") (pin "24") (pinfunction "PF.11_24") (pintype "passive+no_connect"))
    )
    (net (code "118") (name "unconnected-(U4-PG.2-Pad21)") (class "Default")
      (node (ref "U4") (pin "21") (pinfunction "PG.2_21") (pintype "passive+no_connect"))
    )
    (net (code "119") (name "unconnected-(U4-PG.3-Pad22)") (class "Default")
      (node (ref "U4") (pin "22") (pinfunction "PG.3_22") (pintype "passive+no_connect"))
    )
    (net (code "120") (name "unconnected-(U4-PH.6-Pad35)") (class "Default")
      (node (ref "U4") (pin "35") (pinfunction "PH.6_35") (pintype "passive+no_connect"))
    )
    (net (code "121") (name "unconnected-(U4-PH.7-Pad36)") (class "Default")
      (node (ref "U4") (pin "36") (pinfunction "PH.7_36") (pintype "passive+no_connect"))
    )
    (net (code "122") (name "unconnected-(Y3-TRI-STATE-Pad1)") (class "Default")
      (node (ref "Y3") (pin "1") (pinfunction "TRI-STATE_1") (pintype "passive+no_connect"))
    )
  )
)
